# AWSAM_5.net
KiCad netlist of a schematic drawn in Altium Designer
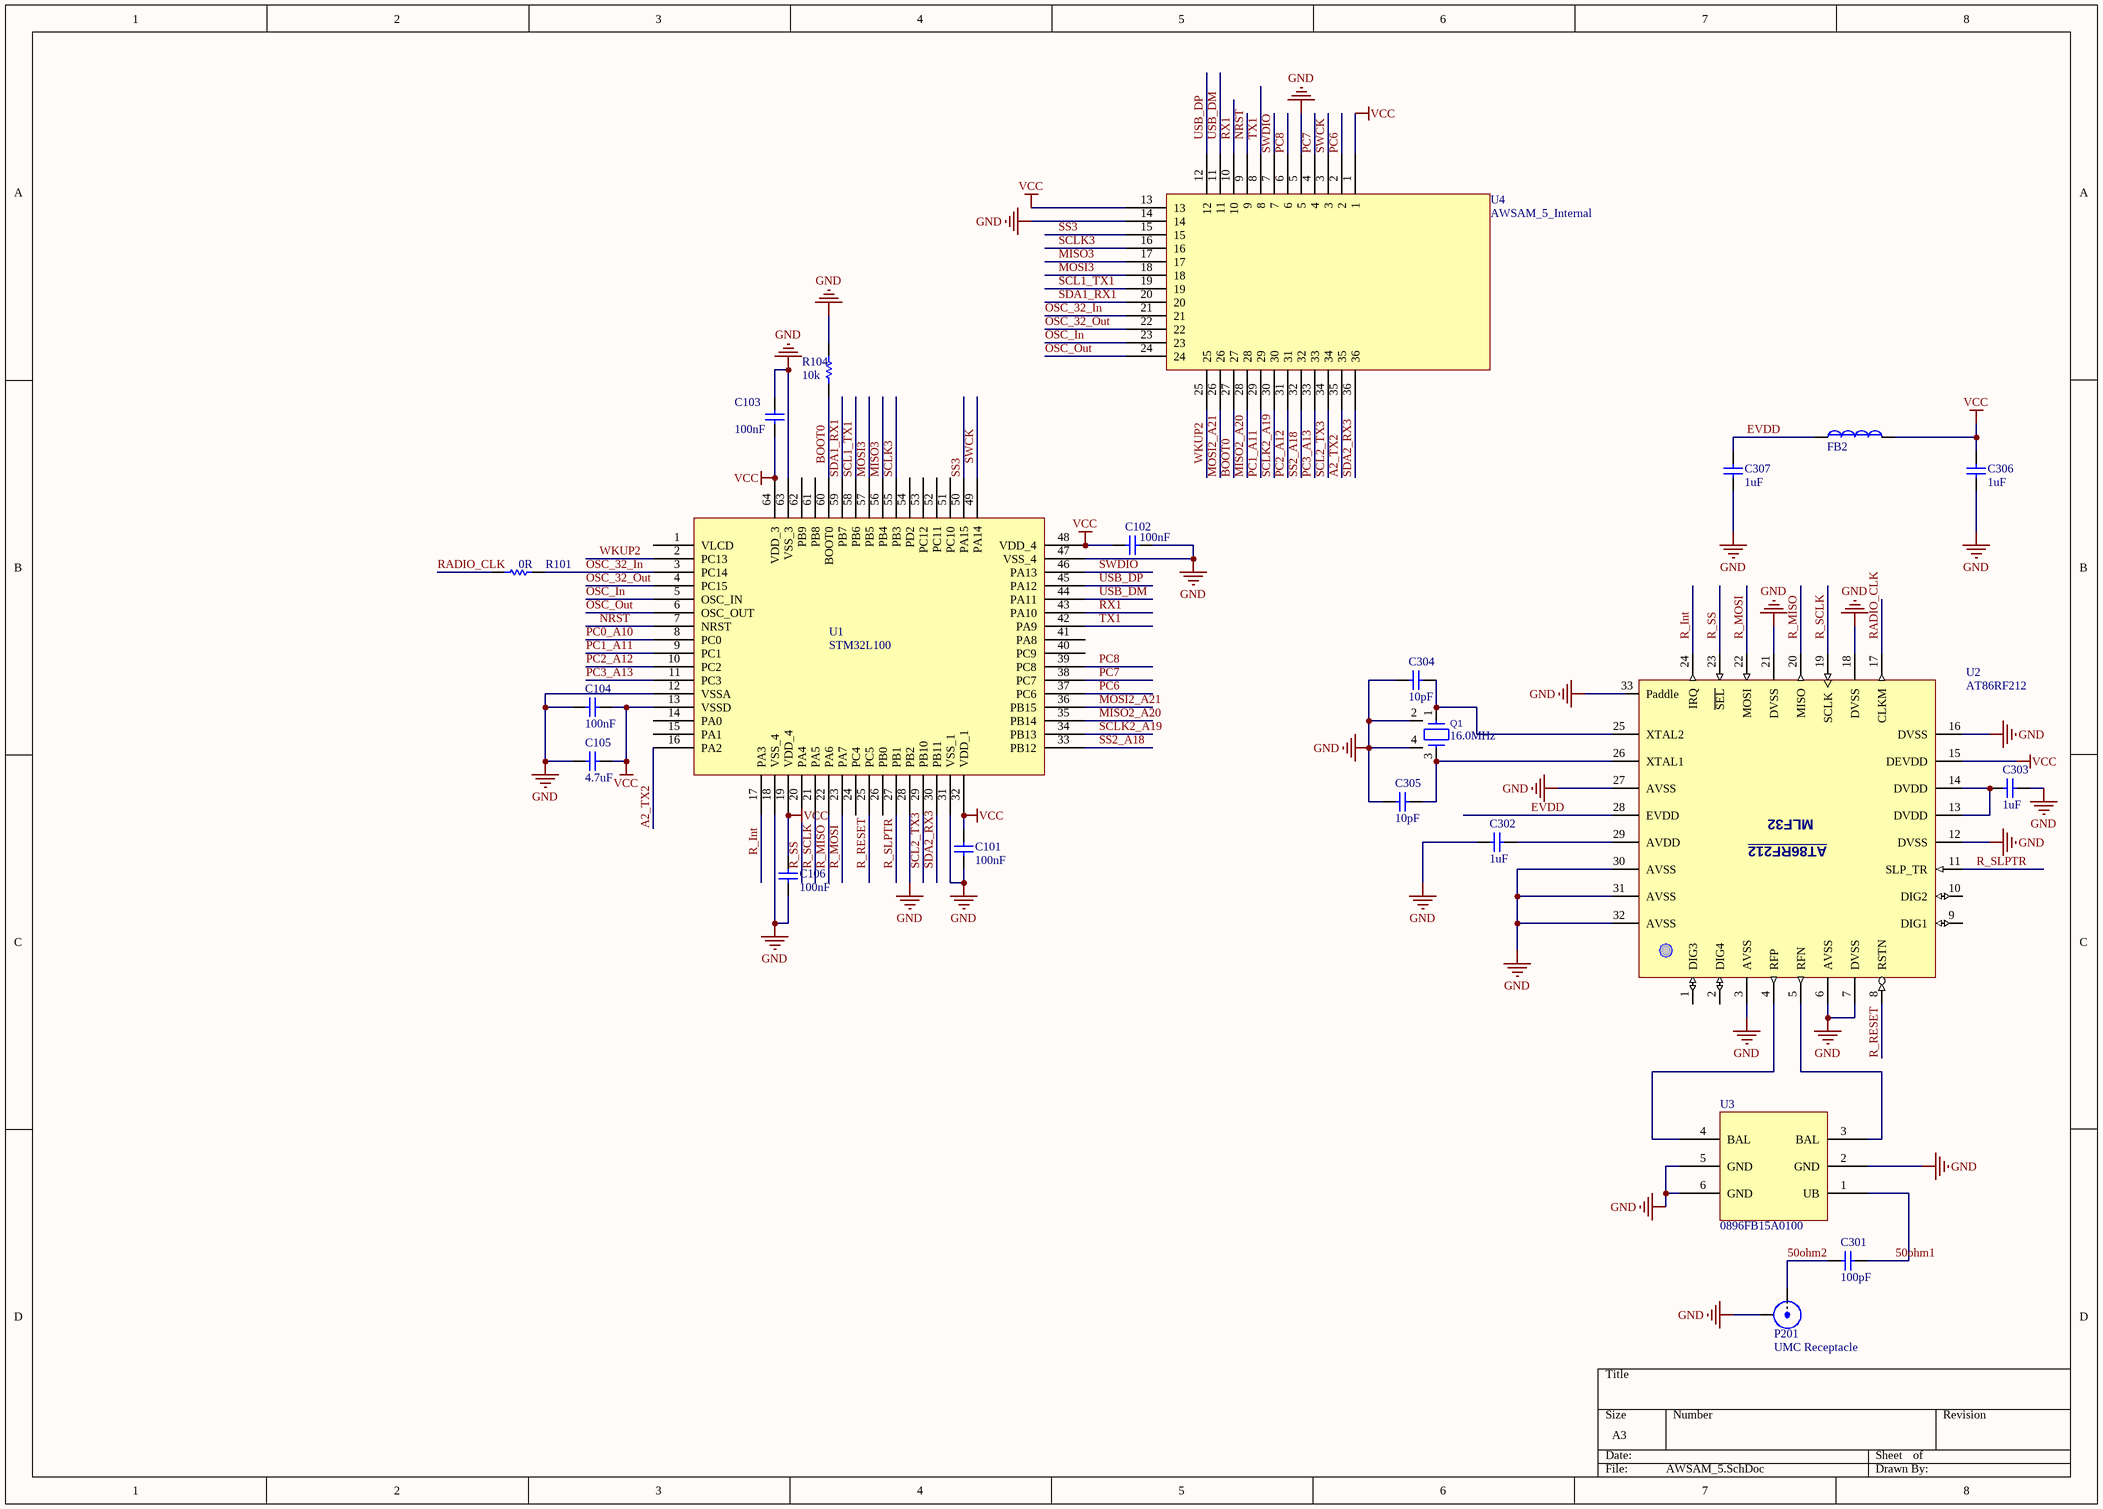
[diagram p0: AWSAM_5.SchDoc]

(export (version "E")
  (design (tool "Eeschema 10.0.6"))
  (components
    (comp (ref "C101")
      (value "100nF")
      (footprint "CAPC1005L")
      (description "GRM155R61A104KA01D")
      (fields
        (field (name "MANUFACTURER") "TDK Corporation")
        (field (name "MANUFACTURER PART NUMBER") "C1608X7R1H222K")
        (field (name "CAPACITANCE") "100nF")
      )
      (libsource (lib "AWSAM-3") (part "C1608X7R1H222K"))
    )
    (comp (ref "C102")
      (value "100nF")
      (footprint "CAPC1005L")
      (description "GRM155R61A104KA01D")
      (fields
        (field (name "MANUFACTURER") "TDK Corporation")
        (field (name "MANUFACTURER PART NUMBER") "C1608X7R1H222K")
        (field (name "CAPACITANCE") "100nF")
      )
      (libsource (lib "AWSAM-3") (part "C1608X7R1H222K"))
    )
    (comp (ref "C103")
      (value "100nF")
      (footprint "CAPC1005L")
      (description "GRM155R61A104KA01D")
      (fields
        (field (name "MANUFACTURER") "TDK Corporation")
        (field (name "MANUFACTURER PART NUMBER") "C1608X7R1H222K")
        (field (name "CAPACITANCE") "100nF")
      )
      (libsource (lib "AWSAM-3") (part "C1608X7R1H222K"))
    )
    (comp (ref "C104")
      (value "100nF")
      (footprint "CAPC1005L")
      (description "GRM155R61A104KA01D")
      (fields
        (field (name "MANUFACTURER") "TDK Corporation")
        (field (name "MANUFACTURER PART NUMBER") "C1608X7R1H222K")
        (field (name "CAPACITANCE") "100nF")
      )
      (libsource (lib "AWSAM-3") (part "C1608X7R1H222K"))
    )
    (comp (ref "C105")
      (value "4.7uF")
      (footprint "CAPC1005L")
      (description "GRM155R60J475ME47D")
      (fields
        (field (name "MANUFACTURER") "TDK Corporation")
        (field (name "MANUFACTURER PART NUMBER") "C1608X7R1H222K")
        (field (name "CAPACITANCE") "4.7uF")
      )
      (libsource (lib "AWSAM-3") (part "C1608X7R1H222K"))
    )
    (comp (ref "C106")
      (value "100nF")
      (footprint "CAPC1005L")
      (description "GRM155R61A104KA01D")
      (fields
        (field (name "MANUFACTURER") "TDK Corporation")
        (field (name "MANUFACTURER PART NUMBER") "C1608X7R1H222K")
        (field (name "CAPACITANCE") "100nF")
      )
      (libsource (lib "AWSAM-3") (part "C1608X7R1H222K"))
    )
    (comp (ref "C301")
      (value "100pF")
      (footprint "CAPC1005L")
      (description "C1005C0G1H101F050BA")
      (fields
        (field (name "MANUFACTURER") "TDK Corporation")
        (field (name "MANUFACTURER PART NUMBER") "C1608X7R1H222K")
        (field (name "CAPACITANCE") "100pF")
      )
      (libsource (lib "AWSAM-3") (part "C1608X7R1H222K"))
    )
    (comp (ref "C302")
      (value "1uF")
      (footprint "CAPC1005L")
      (description "GRM155R60J105KE19D")
      (fields
        (field (name "MANUFACTURER") "TDK Corporation")
        (field (name "MANUFACTURER PART NUMBER") "C1608X7R1H222K")
        (field (name "CAPACITANCE") "1uF")
      )
      (libsource (lib "AWSAM-3") (part "C1608X7R1H222K"))
    )
    (comp (ref "C303")
      (value "1uF")
      (footprint "CAPC1005L")
      (description "GRM155R60J105KE19D")
      (fields
        (field (name "MANUFACTURER") "TDK Corporation")
        (field (name "MANUFACTURER PART NUMBER") "C1608X7R1H222K")
        (field (name "CAPACITANCE") "1uF")
      )
      (libsource (lib "AWSAM-3") (part "C1608X7R1H222K"))
    )
    (comp (ref "C304")
      (value "10pF")
      (footprint "CAPC1005L")
      (description "500R07S100GV4T")
      (fields
        (field (name "MANUFACTURER") "TDK Corporation")
        (field (name "MANUFACTURER PART NUMBER") "C1608X7R1H222K")
        (field (name "CAPACITANCE") "10pF")
      )
      (libsource (lib "AWSAM-3") (part "C1608X7R1H222K"))
    )
    (comp (ref "C305")
      (value "10pF")
      (footprint "CAPC1005L")
      (description "500R07S100GV4T")
      (fields
        (field (name "MANUFACTURER") "TDK Corporation")
        (field (name "MANUFACTURER PART NUMBER") "C1608X7R1H222K")
        (field (name "CAPACITANCE") "10pF")
      )
      (libsource (lib "AWSAM-3") (part "C1608X7R1H222K"))
    )
    (comp (ref "C306")
      (value "1uF")
      (footprint "CAPC1005L")
      (description "GRM155R60J105KE19D")
      (fields
        (field (name "MANUFACTURER") "TDK Corporation")
        (field (name "MANUFACTURER PART NUMBER") "C1608X7R1H222K")
        (field (name "CAPACITANCE") "1uF")
      )
      (libsource (lib "AWSAM-3") (part "C1608X7R1H222K"))
    )
    (comp (ref "C307")
      (value "1uF")
      (footprint "CAPC1005L")
      (description "GRM155R60J105KE19D")
      (fields
        (field (name "MANUFACTURER") "TDK Corporation")
        (field (name "MANUFACTURER PART NUMBER") "C1608X7R1H222K")
        (field (name "CAPACITANCE") "1uF")
      )
      (libsource (lib "AWSAM-3") (part "C1608X7R1H222K"))
    )
    (comp (ref "FB2")
      (value "BLM15AX102SN1D")
      (footprint "IND0402")
      (fields (field (name "MANUFACTURER") "Murata Electronics North America"))
      (libsource (lib "AWSAM-3") (part "BLM15AX102SN1D"))
    )
    (comp (ref "P201")
      (value "UMC Receptacle")
      (footprint "UMC Receptacle")
      (description "128-0711-201")
      (fields (field (name "MANUFACTURER") "Emerson Network Power Connectivity Johnson"))
      (libsource (lib "AWSAM-3") (part "UMC Receptacle"))
    )
    (comp (ref "Q1")
      (value "16.0MHz")
      (footprint "AP7-00061")
      (description "X1E0000210013 TSX-3225 16 MHZ 9.0PF")
      (fields (field (name "TOLERANCE") "15ppm") (field (name "MANUFACTURER") "Epson Toyocom"))
      (libsource (lib "AltiumDbLib") (part "TSX-3225"))
    )
    (comp (ref "R101")
      (value "0R")
      (footprint "RES0402")
      (description "RES 10.0K OHM 1/16W 1% 0402 SMD")
      (fields
        (field (name "MANUFACTURER") "Vishay Dale")
        (field (name "MANUFACTURER PART NUMBER") "CRCW040210K0FKED")
        (field (name "RESISTANCE (OHMS)") "0R")
      )
      (libsource (lib "AWSAM-3") (part "CRCW040210K0FKED"))
    )
    (comp (ref "R104")
      (value "10k")
      (footprint "RES0402")
      (description "MCR01MRTF1002")
      (fields
        (field (name "MANUFACTURER") "Vishay Dale")
        (field (name "MANUFACTURER PART NUMBER") "CRCW040210K0FKED")
        (field (name "RESISTANCE (OHMS)") "10k")
      )
      (libsource (lib "AWSAM-3") (part "CRCW040210K0FKED"))
    )
    (comp (ref "U1")
      (value "STM32L100")
      (footprint "TSQFP50P1200X1200-64L")
      (description "STM32L100RCT6")
      (libsource (lib "STM32L100") (part "STM32L100"))
    )
    (comp (ref "U2")
      (value "AT86RF212")
      (footprint "MLF-32")
      (description "AT86RF212B-ZUR")
      (libsource (lib "Atmel MCU Wireless Library") (part "AT86RF212"))
    )
    (comp (ref "U3")
      (value "0896FB15A0100")
      (footprint "AP3-00048")
      (description "0896FB15A0100E")
      (libsource (lib "0896FB15A0100") (part "0896FB15A0100"))
    )
    (comp (ref "U4")
      (value "AWSAM_5_Internal")
      (footprint "AWSAM_5_Internal")
      (libsource (lib "AWSAM_5") (part "AWSAM_5_Internal"))
    )
  )
  (nets
    (net (code "1") (name "/50ohm1") (class "Default")
      (node (ref "C301") (pin "1") (pinfunction "1_1") (pintype "passive"))
      (node (ref "U3") (pin "1") (pinfunction "UB_1") (pintype "passive"))
    )
    (net (code "2") (name "/50ohm2") (class "Default")
      (node (ref "C301") (pin "2") (pinfunction "2_2") (pintype "passive"))
      (node (ref "P201") (pin "Inner") (pinfunction "Inner_Inner") (pintype "passive"))
    )
    (net (code "3") (name "/A2_TX2") (class "Default")
      (node (ref "U1") (pin "16") (pinfunction "PA2_16") (pintype "passive"))
      (node (ref "U4") (pin "35") (pinfunction "35_35") (pintype "passive"))
    )
    (net (code "4") (name "/BOOT0") (class "Default")
      (node (ref "R104") (pin "2") (pinfunction "2_2") (pintype "passive"))
      (node (ref "U1") (pin "60") (pinfunction "BOOT0_60") (pintype "passive"))
      (node (ref "U4") (pin "27") (pinfunction "27_27") (pintype "passive"))
    )
    (net (code "5") (name "/EVDD") (class "Default")
      (node (ref "C307") (pin "1") (pinfunction "1_1") (pintype "passive"))
      (node (ref "FB2") (pin "1") (pinfunction "1_1") (pintype "passive"))
      (node (ref "U2") (pin "28") (pinfunction "EVDD_28") (pintype "power_in"))
    )
    (net (code "6") (name "/MISO2_A20") (class "Default")
      (node (ref "U1") (pin "35") (pinfunction "PB14_35") (pintype "passive"))
      (node (ref "U4") (pin "28") (pinfunction "28_28") (pintype "passive"))
    )
    (net (code "7") (name "/MISO3") (class "Default")
      (node (ref "U1") (pin "56") (pinfunction "PB4_56") (pintype "passive"))
      (node (ref "U4") (pin "17") (pinfunction "17_17") (pintype "passive"))
    )
    (net (code "8") (name "/MOSI2_A21") (class "Default")
      (node (ref "U1") (pin "36") (pinfunction "PB15_36") (pintype "passive"))
      (node (ref "U4") (pin "26") (pinfunction "26_26") (pintype "passive"))
    )
    (net (code "9") (name "/MOSI3") (class "Default")
      (node (ref "U1") (pin "57") (pinfunction "PB5_57") (pintype "passive"))
      (node (ref "U4") (pin "18") (pinfunction "18_18") (pintype "passive"))
    )
    (net (code "10") (name "/NRST") (class "Default")
      (node (ref "U1") (pin "7") (pinfunction "NRST_7") (pintype "passive"))
      (node (ref "U4") (pin "9") (pinfunction "9_9") (pintype "passive"))
    )
    (net (code "11") (name "/OSC_32_In") (class "Default")
      (node (ref "R101") (pin "2") (pinfunction "2_2") (pintype "passive"))
      (node (ref "U1") (pin "3") (pinfunction "PC14_3") (pintype "passive"))
      (node (ref "U4") (pin "21") (pinfunction "21_21") (pintype "passive"))
    )
    (net (code "12") (name "/OSC_32_Out") (class "Default")
      (node (ref "U1") (pin "4") (pinfunction "PC15_4") (pintype "passive"))
      (node (ref "U4") (pin "22") (pinfunction "22_22") (pintype "passive"))
    )
    (net (code "13") (name "/OSC_In") (class "Default")
      (node (ref "U1") (pin "5") (pinfunction "OSC_IN_5") (pintype "passive"))
      (node (ref "U4") (pin "23") (pinfunction "23_23") (pintype "passive"))
    )
    (net (code "14") (name "/OSC_Out") (class "Default")
      (node (ref "U1") (pin "6") (pinfunction "OSC_OUT_6") (pintype "passive"))
      (node (ref "U4") (pin "24") (pinfunction "24_24") (pintype "passive"))
    )
    (net (code "15") (name "/PC0_A10") (class "Default")
      (node (ref "U1") (pin "8") (pinfunction "PC0_8") (pintype "passive"))
    )
    (net (code "16") (name "/PC1_A11") (class "Default")
      (node (ref "U1") (pin "9") (pinfunction "PC1_9") (pintype "passive"))
      (node (ref "U4") (pin "29") (pinfunction "29_29") (pintype "passive"))
    )
    (net (code "17") (name "/PC2_A12") (class "Default")
      (node (ref "U1") (pin "10") (pinfunction "PC2_10") (pintype "passive"))
      (node (ref "U4") (pin "31") (pinfunction "31_31") (pintype "passive"))
    )
    (net (code "18") (name "/PC3_A13") (class "Default")
      (node (ref "U1") (pin "11") (pinfunction "PC3_11") (pintype "passive"))
      (node (ref "U4") (pin "33") (pinfunction "33_33") (pintype "passive"))
    )
    (net (code "19") (name "/PC6") (class "Default")
      (node (ref "U1") (pin "37") (pinfunction "PC6_37") (pintype "passive"))
      (node (ref "U4") (pin "2") (pinfunction "2_2") (pintype "passive"))
    )
    (net (code "20") (name "/PC7") (class "Default")
      (node (ref "U1") (pin "38") (pinfunction "PC7_38") (pintype "passive"))
      (node (ref "U4") (pin "4") (pinfunction "4_4") (pintype "passive"))
    )
    (net (code "21") (name "/PC8") (class "Default")
      (node (ref "U1") (pin "39") (pinfunction "PC8_39") (pintype "passive"))
      (node (ref "U4") (pin "6") (pinfunction "6_6") (pintype "passive"))
    )
    (net (code "22") (name "/RADIO_CLK") (class "Default")
      (node (ref "R101") (pin "1") (pinfunction "1_1") (pintype "passive"))
      (node (ref "U2") (pin "17") (pinfunction "CLKM_17") (pintype "output"))
    )
    (net (code "23") (name "/RX1") (class "Default")
      (node (ref "U1") (pin "43") (pinfunction "PA10_43") (pintype "passive"))
      (node (ref "U4") (pin "10") (pinfunction "10_10") (pintype "passive"))
    )
    (net (code "24") (name "/R_Int") (class "Default")
      (node (ref "U1") (pin "17") (pinfunction "PA3_17") (pintype "passive"))
      (node (ref "U2") (pin "24") (pinfunction "IRQ_24") (pintype "output"))
    )
    (net (code "25") (name "/R_MISO") (class "Default")
      (node (ref "U1") (pin "22") (pinfunction "PA6_22") (pintype "passive"))
      (node (ref "U2") (pin "20") (pinfunction "MISO_20") (pintype "output"))
    )
    (net (code "26") (name "/R_MOSI") (class "Default")
      (node (ref "U1") (pin "23") (pinfunction "PA7_23") (pintype "passive"))
      (node (ref "U2") (pin "22") (pinfunction "MOSI_22") (pintype "input"))
    )
    (net (code "27") (name "/R_RESET") (class "Default")
      (node (ref "U1") (pin "25") (pinfunction "PC5_25") (pintype "passive"))
      (node (ref "U2") (pin "8") (pinfunction "RSTN_8") (pintype "input"))
    )
    (net (code "28") (name "/R_SCLK") (class "Default")
      (node (ref "U1") (pin "21") (pinfunction "PA5_21") (pintype "passive"))
      (node (ref "U2") (pin "19") (pinfunction "SCLK_19") (pintype "input"))
    )
    (net (code "29") (name "/R_SLPTR") (class "Default")
      (node (ref "U1") (pin "27") (pinfunction "PB1_27") (pintype "passive"))
      (node (ref "U2") (pin "11") (pinfunction "SLP_TR_11") (pintype "input"))
    )
    (net (code "30") (name "/R_SS") (class "Default")
      (node (ref "U1") (pin "20") (pinfunction "PA4_20") (pintype "passive"))
      (node (ref "U2") (pin "23") (pinfunction "~{SEL}_23") (pintype "input"))
    )
    (net (code "31") (name "/SCL1_TX1") (class "Default")
      (node (ref "U1") (pin "58") (pinfunction "PB6_58") (pintype "passive"))
      (node (ref "U4") (pin "19") (pinfunction "19_19") (pintype "passive"))
    )
    (net (code "32") (name "/SCL2_TX3") (class "Default")
      (node (ref "U1") (pin "29") (pinfunction "PB10_29") (pintype "passive"))
      (node (ref "U4") (pin "34") (pinfunction "34_34") (pintype "passive"))
    )
    (net (code "33") (name "/SCLK2_A19") (class "Default")
      (node (ref "U1") (pin "34") (pinfunction "PB13_34") (pintype "passive"))
      (node (ref "U4") (pin "30") (pinfunction "30_30") (pintype "passive"))
    )
    (net (code "34") (name "/SCLK3") (class "Default")
      (node (ref "U1") (pin "55") (pinfunction "PB3_55") (pintype "passive"))
      (node (ref "U4") (pin "16") (pinfunction "16_16") (pintype "passive"))
    )
    (net (code "35") (name "/SDA1_RX1") (class "Default")
      (node (ref "U1") (pin "59") (pinfunction "PB7_59") (pintype "passive"))
      (node (ref "U4") (pin "20") (pinfunction "20_20") (pintype "passive"))
    )
    (net (code "36") (name "/SDA2_RX3") (class "Default")
      (node (ref "U1") (pin "30") (pinfunction "PB11_30") (pintype "passive"))
      (node (ref "U4") (pin "36") (pinfunction "36_36") (pintype "passive"))
    )
    (net (code "37") (name "/SS2_A18") (class "Default")
      (node (ref "U1") (pin "33") (pinfunction "PB12_33") (pintype "passive"))
      (node (ref "U4") (pin "32") (pinfunction "32_32") (pintype "passive"))
    )
    (net (code "38") (name "/SS3") (class "Default")
      (node (ref "U1") (pin "50") (pinfunction "PA15_50") (pintype "passive"))
      (node (ref "U4") (pin "15") (pinfunction "15_15") (pintype "passive"))
    )
    (net (code "39") (name "/SWCK") (class "Default")
      (node (ref "U1") (pin "49") (pinfunction "PA14_49") (pintype "passive"))
      (node (ref "U4") (pin "3") (pinfunction "3_3") (pintype "passive"))
    )
    (net (code "40") (name "/SWDIO") (class "Default")
      (node (ref "U1") (pin "46") (pinfunction "PA13_46") (pintype "passive"))
      (node (ref "U4") (pin "7") (pinfunction "7_7") (pintype "passive"))
    )
    (net (code "41") (name "/TX1") (class "Default")
      (node (ref "U1") (pin "42") (pinfunction "PA9_42") (pintype "passive"))
      (node (ref "U4") (pin "8") (pinfunction "8_8") (pintype "passive"))
    )
    (net (code "42") (name "/USB_DM") (class "Default")
      (node (ref "U1") (pin "44") (pinfunction "PA11_44") (pintype "passive"))
      (node (ref "U4") (pin "11") (pinfunction "11_11") (pintype "passive"))
    )
    (net (code "43") (name "/USB_DP") (class "Default")
      (node (ref "U1") (pin "45") (pinfunction "PA12_45") (pintype "passive"))
      (node (ref "U4") (pin "12") (pinfunction "12_12") (pintype "passive"))
    )
    (net (code "44") (name "/WKUP2") (class "Default")
      (node (ref "U1") (pin "2") (pinfunction "PC13_2") (pintype "passive"))
      (node (ref "U4") (pin "25") (pinfunction "25_25") (pintype "passive"))
    )
    (net (code "45") (name "GND") (class "Default")
      (node (ref "C101") (pin "2") (pinfunction "2_2") (pintype "passive"))
      (node (ref "C102") (pin "2") (pinfunction "2_2") (pintype "passive"))
      (node (ref "C103") (pin "1") (pinfunction "1_1") (pintype "passive"))
      (node (ref "C104") (pin "1") (pinfunction "1_1") (pintype "passive"))
      (node (ref "C105") (pin "1") (pinfunction "1_1") (pintype "passive"))
      (node (ref "C106") (pin "1") (pinfunction "1_1") (pintype "passive"))
      (node (ref "C302") (pin "2") (pinfunction "2_2") (pintype "passive"))
      (node (ref "C303") (pin "1") (pinfunction "1_1") (pintype "passive"))
      (node (ref "C304") (pin "1") (pinfunction "1_1") (pintype "passive"))
      (node (ref "C305") (pin "2") (pinfunction "2_2") (pintype "passive"))
      (node (ref "C306") (pin "2") (pinfunction "2_2") (pintype "passive"))
      (node (ref "C307") (pin "2") (pinfunction "2_2") (pintype "passive"))
      (node (ref "P201") (pin "Outer") (pinfunction "Outer_Outer") (pintype "passive"))
      (node (ref "Q1") (pin "2") (pinfunction "GND_2") (pintype "passive"))
      (node (ref "Q1") (pin "4") (pinfunction "GND_4") (pintype "passive"))
      (node (ref "R104") (pin "1") (pinfunction "1_1") (pintype "passive"))
      (node (ref "U1") (pin "12") (pinfunction "VSSA_12") (pintype "passive"))
      (node (ref "U1") (pin "18") (pinfunction "VSS_4_18") (pintype "passive"))
      (node (ref "U1") (pin "28") (pinfunction "PB2_28") (pintype "passive"))
      (node (ref "U1") (pin "31") (pinfunction "VSS_1_31") (pintype "passive"))
      (node (ref "U1") (pin "47") (pinfunction "VSS_4_47") (pintype "passive"))
      (node (ref "U1") (pin "63") (pinfunction "VSS_3_63") (pintype "passive"))
      (node (ref "U2") (pin "12") (pinfunction "DVSS_12") (pintype "power_in"))
      (node (ref "U2") (pin "16") (pinfunction "DVSS_16") (pintype "power_in"))
      (node (ref "U2") (pin "18") (pinfunction "DVSS_18") (pintype "power_in"))
      (node (ref "U2") (pin "21") (pinfunction "DVSS_21") (pintype "power_in"))
      (node (ref "U2") (pin "27") (pinfunction "AVSS_27") (pintype "power_in"))
      (node (ref "U2") (pin "3") (pinfunction "AVSS_3") (pintype "power_in"))
      (node (ref "U2") (pin "30") (pinfunction "AVSS_30") (pintype "power_in"))
      (node (ref "U2") (pin "31") (pinfunction "AVSS_31") (pintype "passive"))
      (node (ref "U2") (pin "32") (pinfunction "AVSS_32") (pintype "passive"))
      (node (ref "U2") (pin "33") (pinfunction "Paddle_33") (pintype "passive"))
      (node (ref "U2") (pin "6") (pinfunction "AVSS_6") (pintype "power_in"))
      (node (ref "U2") (pin "7") (pinfunction "DVSS_7") (pintype "passive"))
      (node (ref "U3") (pin "2") (pinfunction "GND_2") (pintype "passive"))
      (node (ref "U3") (pin "5") (pinfunction "GND_5") (pintype "passive"))
      (node (ref "U3") (pin "6") (pinfunction "GND_6") (pintype "passive"))
      (node (ref "U4") (pin "14") (pinfunction "14_14") (pintype "passive"))
      (node (ref "U4") (pin "5") (pinfunction "5_5") (pintype "passive"))
    )
    (net (code "46") (name "Net-(C303-Pad2)") (class "Default")
      (node (ref "C303") (pin "2") (pinfunction "2_2") (pintype "passive"))
      (node (ref "U2") (pin "13") (pinfunction "DVDD_13") (pintype "power_in"))
      (node (ref "U2") (pin "14") (pinfunction "DVDD_14") (pintype "power_in"))
    )
    (net (code "47") (name "Net-(Q1-IN)") (class "Default")
      (node (ref "C304") (pin "2") (pinfunction "2_2") (pintype "passive"))
      (node (ref "Q1") (pin "1") (pinfunction "IN_1") (pintype "passive"))
      (node (ref "U2") (pin "25") (pinfunction "XTAL2_25") (pintype "passive"))
    )
    (net (code "48") (name "Net-(Q1-OUT)") (class "Default")
      (node (ref "C305") (pin "1") (pinfunction "1_1") (pintype "passive"))
      (node (ref "Q1") (pin "3") (pinfunction "OUT_3") (pintype "passive"))
      (node (ref "U2") (pin "26") (pinfunction "XTAL1_26") (pintype "passive"))
    )
    (net (code "49") (name "Net-(U2-AVDD)") (class "Default")
      (node (ref "C302") (pin "1") (pinfunction "1_1") (pintype "passive"))
      (node (ref "U2") (pin "29") (pinfunction "AVDD_29") (pintype "power_in"))
    )
    (net (code "50") (name "Net-(U2-RFN)") (class "Default")
      (node (ref "U2") (pin "5") (pinfunction "RFN_5") (pintype "output"))
      (node (ref "U3") (pin "3") (pinfunction "BAL_3") (pintype "passive"))
    )
    (net (code "51") (name "Net-(U2-RFP)") (class "Default")
      (node (ref "U2") (pin "4") (pinfunction "RFP_4") (pintype "output"))
      (node (ref "U3") (pin "4") (pinfunction "BAL_4") (pintype "passive"))
    )
    (net (code "52") (name "VCC") (class "Default")
      (node (ref "C101") (pin "1") (pinfunction "1_1") (pintype "passive"))
      (node (ref "C102") (pin "1") (pinfunction "1_1") (pintype "passive"))
      (node (ref "C103") (pin "2") (pinfunction "2_2") (pintype "passive"))
      (node (ref "C104") (pin "2") (pinfunction "2_2") (pintype "passive"))
      (node (ref "C105") (pin "2") (pinfunction "2_2") (pintype "passive"))
      (node (ref "C106") (pin "2") (pinfunction "2_2") (pintype "passive"))
      (node (ref "C306") (pin "1") (pinfunction "1_1") (pintype "passive"))
      (node (ref "FB2") (pin "2") (pinfunction "2_2") (pintype "passive"))
      (node (ref "U1") (pin "13") (pinfunction "VSSD_13") (pintype "passive"))
      (node (ref "U1") (pin "19") (pinfunction "VDD_4_19") (pintype "passive"))
      (node (ref "U1") (pin "32") (pinfunction "VDD_1_32") (pintype "passive"))
      (node (ref "U1") (pin "48") (pinfunction "VDD_4_48") (pintype "passive"))
      (node (ref "U1") (pin "64") (pinfunction "VDD_3_64") (pintype "passive"))
      (node (ref "U2") (pin "15") (pinfunction "DEVDD_15") (pintype "power_in"))
      (node (ref "U4") (pin "1") (pinfunction "1_1") (pintype "passive"))
      (node (ref "U4") (pin "13") (pinfunction "13_13") (pintype "passive"))
    )
    (net (code "53") (name "unconnected-(U1-PA0-Pad14)") (class "Default")
      (node (ref "U1") (pin "14") (pinfunction "PA0_14") (pintype "passive"))
    )
    (net (code "54") (name "unconnected-(U1-PA1-Pad15)") (class "Default")
      (node (ref "U1") (pin "15") (pinfunction "PA1_15") (pintype "passive"))
    )
    (net (code "55") (name "unconnected-(U1-PA8-Pad41)") (class "Default")
      (node (ref "U1") (pin "41") (pinfunction "PA8_41") (pintype "passive"))
    )
    (net (code "56") (name "unconnected-(U1-PB0-Pad26)") (class "Default")
      (node (ref "U1") (pin "26") (pinfunction "PB0_26") (pintype "passive"))
    )
    (net (code "57") (name "unconnected-(U1-PB8-Pad61)") (class "Default")
      (node (ref "U1") (pin "61") (pinfunction "PB8_61") (pintype "passive"))
    )
    (net (code "58") (name "unconnected-(U1-PB9-Pad62)") (class "Default")
      (node (ref "U1") (pin "62") (pinfunction "PB9_62") (pintype "passive"))
    )
    (net (code "59") (name "unconnected-(U1-PC4-Pad24)") (class "Default")
      (node (ref "U1") (pin "24") (pinfunction "PC4_24") (pintype "passive"))
    )
    (net (code "60") (name "unconnected-(U1-PC9-Pad40)") (class "Default")
      (node (ref "U1") (pin "40") (pinfunction "PC9_40") (pintype "passive"))
    )
    (net (code "61") (name "unconnected-(U1-PC10-Pad51)") (class "Default")
      (node (ref "U1") (pin "51") (pinfunction "PC10_51") (pintype "passive"))
    )
    (net (code "62") (name "unconnected-(U1-PC11-Pad52)") (class "Default")
      (node (ref "U1") (pin "52") (pinfunction "PC11_52") (pintype "passive"))
    )
    (net (code "63") (name "unconnected-(U1-PC12-Pad53)") (class "Default")
      (node (ref "U1") (pin "53") (pinfunction "PC12_53") (pintype "passive"))
    )
    (net (code "64") (name "unconnected-(U1-PD2-Pad54)") (class "Default")
      (node (ref "U1") (pin "54") (pinfunction "PD2_54") (pintype "passive"))
    )
    (net (code "65") (name "unconnected-(U1-VLCD-Pad1)") (class "Default")
      (node (ref "U1") (pin "1") (pinfunction "VLCD_1") (pintype "passive"))
    )
    (net (code "66") (name "unconnected-(U2-DIG1-Pad9)") (class "Default")
      (node (ref "U2") (pin "9") (pinfunction "DIG1_9") (pintype "bidirectional"))
    )
    (net (code "67") (name "unconnected-(U2-DIG2-Pad10)") (class "Default")
      (node (ref "U2") (pin "10") (pinfunction "DIG2_10") (pintype "bidirectional"))
    )
    (net (code "68") (name "unconnected-(U2-DIG3-Pad1)") (class "Default")
      (node (ref "U2") (pin "1") (pinfunction "DIG3_1") (pintype "bidirectional"))
    )
    (net (code "69") (name "unconnected-(U2-DIG4-Pad2)") (class "Default")
      (node (ref "U2") (pin "2") (pinfunction "DIG4_2") (pintype "bidirectional"))
    )
  )
)
